# AT_Link_V1_4.net
KiCad netlist of a schematic drawn in Altium Designer
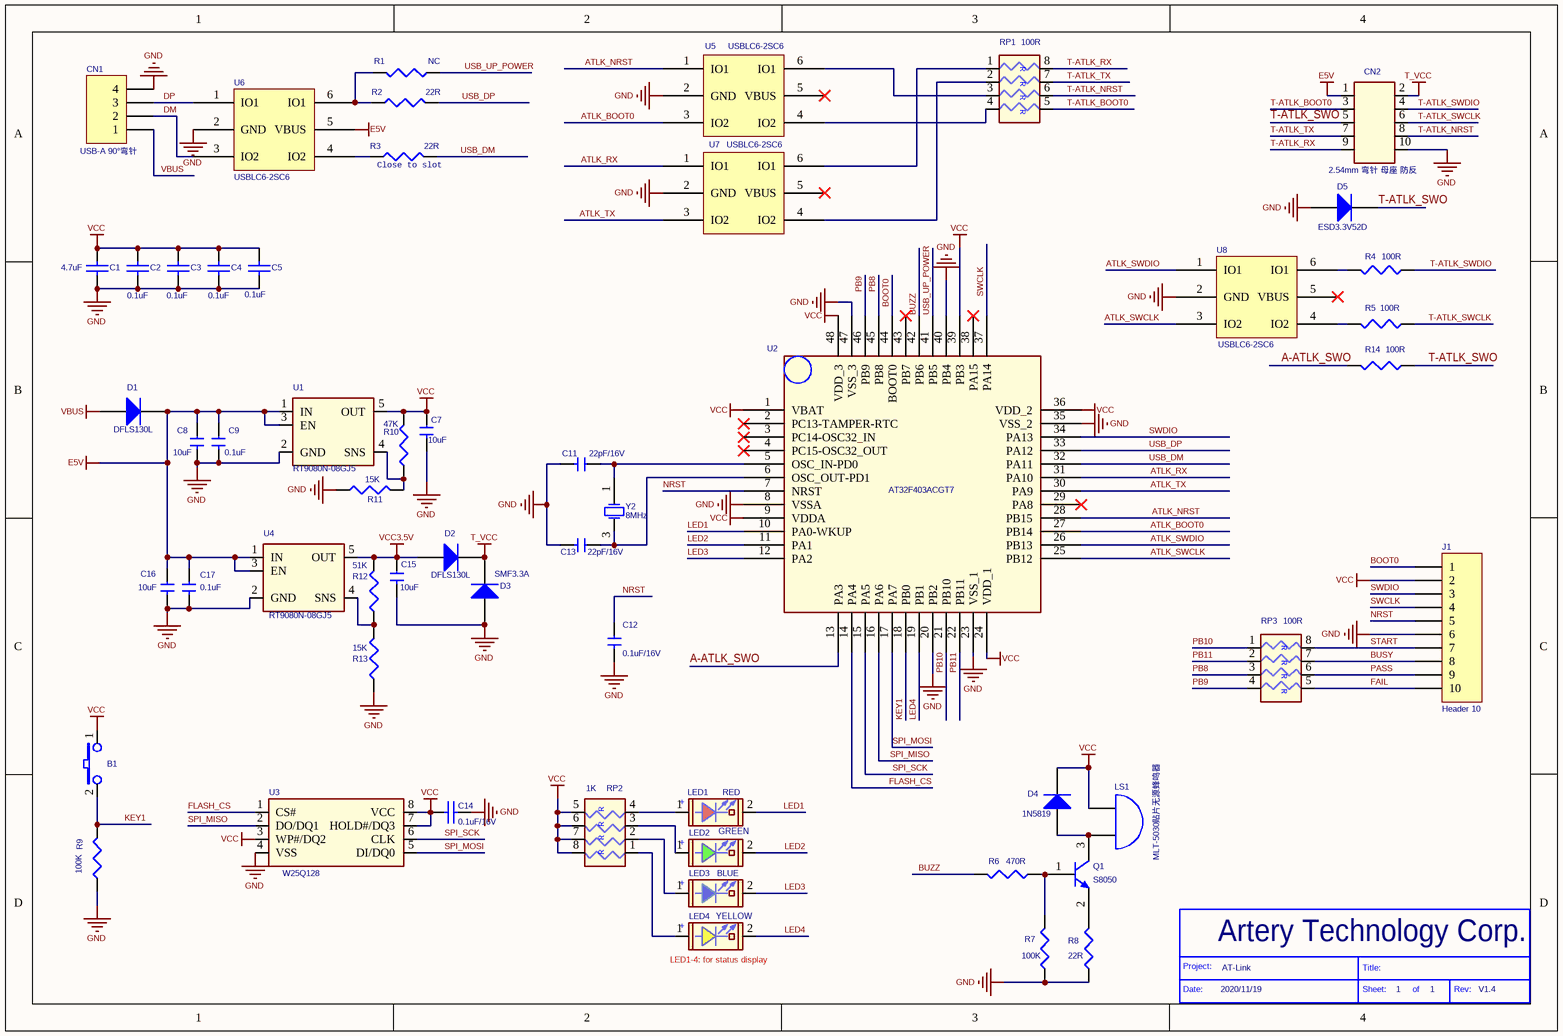
[diagram p0: AT_Link_V1.4.SchDoc]

(export (version "E")
  (design (tool "Eeschema 10.0.6"))
  (components
    (comp (ref "B1")
      (value "PB,Blue,SMD_2P")
      (description "3*6*5")
      (libsource (lib "*") (part "Push_Bottom,Blue,SMD_2P"))
    )
    (comp (ref "C1")
      (value "4.7uF")
      (footprint "C0603")
      (description "Capacitor (Semiconductor SIM Model)")
      (fields (field (name "PUBLISHER") "Altium Limited"))
      (libsource (lib "PcbLib") (part "Cap Semi"))
    )
    (comp (ref "C2")
      (value "0.1uF")
      (footprint "C0603")
      (description "Capacitor (Semiconductor SIM Model)")
      (fields (field (name "PUBLISHER") "Altium Limited"))
      (libsource (lib "PcbLib") (part "Cap Semi"))
    )
    (comp (ref "C3")
      (value "0.1uF")
      (footprint "C0603")
      (description "Capacitor (Semiconductor SIM Model)")
      (fields (field (name "PUBLISHER") "Altium Limited"))
      (libsource (lib "PcbLib") (part "Cap Semi"))
    )
    (comp (ref "C4")
      (value "0.1uF")
      (footprint "C0603")
      (description "Capacitor (Semiconductor SIM Model)")
      (fields (field (name "PUBLISHER") "Altium Limited"))
      (libsource (lib "PcbLib") (part "Cap Semi"))
    )
    (comp (ref "C5")
      (value "0.1uF")
      (footprint "C0603")
      (description "Capacitor (Semiconductor SIM Model)")
      (fields (field (name "PUBLISHER") "Altium Limited"))
      (libsource (lib "PcbLib") (part "Cap Semi"))
    )
    (comp (ref "C7") (value "10uF") (libsource (lib "*") (part "0.1uF,50V,20%,SMD0603")))
    (comp (ref "C8") (value "10uF") (libsource (lib "*") (part "0.1uF,50V,20%,SMD0603")))
    (comp (ref "C9") (value "0.1uF") (libsource (lib "*") (part "0.1uF,50V,20%,SMD0603")))
    (comp (ref "C11") (value "22pF/16V") (libsource (lib "*") (part "10pF,50V,5%,SMD0603")))
    (comp (ref "C12") (value "0.1uF/16V") (libsource (lib "*") (part "0.1uF,50V,20%,SMD0603")))
    (comp (ref "C13") (value "22pF/16V") (libsource (lib "*") (part "10pF,50V,5%,SMD0603")))
    (comp (ref "C14")
      (value "0.1uF/16V")
      (footprint "C0603")
      (description "Capacitor (Semiconductor SIM Model)")
      (fields (field (name "PUBLISHER") "Altium Limited"))
      (libsource (lib "PcbLib") (part "Cap Semi"))
    )
    (comp (ref "C15") (value "10uF") (libsource (lib "*") (part "0.1uF,50V,20%,SMD0603")))
    (comp (ref "C16") (value "10uF") (libsource (lib "*") (part "0.1uF,50V,20%,SMD0603")))
    (comp (ref "C17") (value "0.1uF") (libsource (lib "*") (part "0.1uF,50V,20%,SMD0603")))
    (comp (ref "CN1")
      (value "USB-A 90°弯针")
      (footprint "USB_A - Dip")
      (description "Header, 4-Pin")
      (fields (field (name "PUBLISHER") "Altium Limited"))
      (libsource (lib "Miscellaneous Connectors") (part "Header 4"))
    )
    (comp (ref "CN2") (value "CON1") (footprint "SWD_2*5P_SMT") (libsource (lib "*") (part "CON10A_0")))
    (comp (ref "D1")
      (value "DFLS130L")
      (footprint "SOD-123")
      (description "Default Diode")
      (fields (field (name "PUBLISHER") "Altium Limited"))
      (libsource (lib "Miscellaneous Devices") (part "Diode"))
    )
    (comp (ref "D2")
      (value "DFLS130L")
      (footprint "SOD-123")
      (description "Default Diode")
      (fields (field (name "PUBLISHER") "Altium Limited"))
      (libsource (lib "Miscellaneous Devices") (part "Diode"))
    )
    (comp (ref "D3")
      (value "SMF3.3A")
      (footprint "SOD-123")
      (description "Default Diode")
      (fields (field (name "PUBLISHER") "Altium Limited"))
      (libsource (lib "Miscellaneous Devices") (part "Diode"))
    )
    (comp (ref "D4")
      (value "1N5819")
      (footprint "LED0603")
      (description "Default Diode")
      (fields (field (name "PUBLISHER") "Altium Limited"))
      (libsource (lib "Miscellaneous Devices") (part "Diode"))
    )
    (comp (ref "D5")
      (value "ESD3.3V52D")
      (footprint "SOD523")
      (description "Default Diode")
      (fields (field (name "PUBLISHER") "Altium Limited"))
      (libsource (lib "Miscellaneous Devices") (part "Diode"))
    )
    (comp (ref "J1")
      (value "Header 10")
      (footprint "HDR1X10")
      (description "Header, 10-Pin")
      (fields (field (name "PUBLISHER") "Altium Limited"))
      (libsource (lib "Miscellaneous Connectors") (part "Header 10"))
    )
    (comp (ref "LED1")
      (value "RED")
      (footprint "LED0603")
      (libsource (lib "AT32F403_TINY_LQFP144_Library") (part "RED,SMD0603"))
    )
    (comp (ref "LED2")
      (value "GREEN")
      (footprint "LED0603")
      (libsource (lib "AT32F403_TINY_LQFP144_Library") (part "GREEN,SMD0603"))
    )
    (comp (ref "LED3")
      (value "BLUE")
      (footprint "LED0603")
      (description "贴片LED 蓝色 0603")
      (libsource (lib "AT_START_F415") (part "BLUE,SMD0603"))
    )
    (comp (ref "LED4")
      (value "YELLOW")
      (footprint "LED0603")
      (libsource (lib "Schlib1") (part "YELLOW,SMD0603"))
    )
    (comp (ref "LS1")
      (value "MLT-5030贴片无源蜂鸣器")
      (footprint "BUZZER - 5030")
      (description "Electrical Bell")
      (fields (field (name "PUBLISHER") "Altium Limited"))
      (libsource (lib "Miscellaneous Devices") (part "Bell"))
    )
    (comp (ref "Q1") (value "S8050") (footprint "SOT-23") (libsource (lib "Schlib") (part "NPN")))
    (comp (ref "R1") (value "NC") (libsource (lib "*") (part "10K,1/10W,1%,SMD0603_Dup1")))
    (comp (ref "R2") (value "22R") (libsource (lib "*") (part "22,1/10W,1%,SMD0603")))
    (comp (ref "R3") (value "22R") (libsource (lib "*") (part "22,1/10W,1%,SMD0603")))
    (comp (ref "R4") (value "100R") (libsource (lib "*") (part "22,1/10W,1%,SMD0603")))
    (comp (ref "R5") (value "100R") (libsource (lib "*") (part "22,1/10W,1%,SMD0603")))
    (comp (ref "R6") (value "470R") (libsource (lib "*") (part "470,1/10W,1%,SMD0603")))
    (comp (ref "R7") (value "100K") (libsource (lib "*") (part "470,1/10W,1%,SMD0603")))
    (comp (ref "R8") (value "22R") (libsource (lib "*") (part "470,1/10W,1%,SMD0603")))
    (comp (ref "R9") (value "100K") (libsource (lib "*") (part "10K,1/10W,1%,SMD0603")))
    (comp (ref "R10") (value "47K") (libsource (lib "*") (part "470,1/10W,1%,SMD0603")))
    (comp (ref "R11") (value "15K") (libsource (lib "*") (part "470,1/10W,1%,SMD0603")))
    (comp (ref "R12") (value "51K") (libsource (lib "*") (part "470,1/10W,1%,SMD0603")))
    (comp (ref "R13") (value "15K") (libsource (lib "*") (part "470,1/10W,1%,SMD0603")))
    (comp (ref "R14") (value "100R") (libsource (lib "*") (part "22,1/10W,1%,SMD0603")))
    (comp (ref "RP1") (value "100R") (libsource (lib "") (part "22,1/16W,5%,8P4R_1")))
    (comp (ref "RP2") (value "1K") (libsource (lib "*") (part "22,1/16W,5%,8P4R")))
    (comp (ref "RP3") (value "100R") (libsource (lib "") (part "22,1/16W,5%,8P4R_1")))
    (comp (ref "U1") (value "RT9080N-08GJ5") (libsource (lib "SCM_START_402F") (part "RT9080N")))
    (comp (ref "U2")
      (value "AT32F403ACGT7")
      (footprint "AT403-ALL-PcbLib:LQFP48 - 2")
      (libsource (lib "AT403-ALL-Package") (part "LQFP48&QFN48"))
    )
    (comp (ref "U3")
      (value "W25Q128")
      (footprint "SOIC8_208")
      (libsource (lib "AT32F403_TINY_LQFP144_Library") (part "W25Q128FVSIQ,SOIC8_1"))
    )
    (comp (ref "U4") (value "RT9080N-08GJ5") (libsource (lib "SCM_START_402F") (part "RT9080N")))
    (comp (ref "U5")
      (value "USBLC6-2SC6")
      (footprint "SOT23_6P - L")
      (libsource (lib "Schlib1") (part "USBLC6-2SC6"))
    )
    (comp (ref "U6")
      (value "USBLC6-2SC6")
      (footprint "SOT23_6P - L")
      (libsource (lib "Schlib1") (part "USBLC6-2SC6"))
    )
    (comp (ref "U7")
      (value "USBLC6-2SC6")
      (footprint "SOT23_6P - L")
      (libsource (lib "Schlib1") (part "USBLC6-2SC6"))
    )
    (comp (ref "U8")
      (value "USBLC6-2SC6")
      (footprint "SOT23_6P - L")
      (libsource (lib "Schlib1") (part "USBLC6-2SC6"))
    )
    (comp (ref "Y2")
      (value "8MHz")
      (footprint "XTAL_5032")
      (description "贴片晶振")
      (libsource (lib "Artery_Wanbing") (part "SMD-5032_4P  8MHZ 20PF 10PPM"))
    )
  )
  (nets
    (net (code "1") (name "/A-ATLK_SWO") (class "Default")
      (node (ref "R14") (pin "2") (pinfunction "2_2") (pintype "passive"))
      (node (ref "U2") (pin "13") (pinfunction "PA3_13") (pintype "passive"))
    )
    (net (code "2") (name "/ATLK_BOOT0") (class "Default")
      (node (ref "U2") (pin "27") (pinfunction "PB14_27") (pintype "passive"))
      (node (ref "U5") (pin "3") (pinfunction "IO2_3") (pintype "passive"))
    )
    (net (code "3") (name "/ATLK_NRST") (class "Default")
      (node (ref "U2") (pin "28") (pinfunction "PB15_28") (pintype "passive"))
      (node (ref "U5") (pin "1") (pinfunction "IO1_1") (pintype "passive"))
    )
    (net (code "4") (name "/ATLK_RX") (class "Default")
      (node (ref "U2") (pin "31") (pinfunction "PA10_31") (pintype "passive"))
      (node (ref "U7") (pin "1") (pinfunction "IO1_1") (pintype "passive"))
    )
    (net (code "5") (name "/ATLK_SWCLK") (class "Default")
      (node (ref "U2") (pin "25") (pinfunction "PB12_25") (pintype "passive"))
      (node (ref "U8") (pin "3") (pinfunction "IO2_3") (pintype "passive"))
    )
    (net (code "6") (name "/ATLK_SWDIO") (class "Default")
      (node (ref "U2") (pin "26") (pinfunction "PB13_26") (pintype "passive"))
      (node (ref "U8") (pin "1") (pinfunction "IO1_1") (pintype "passive"))
    )
    (net (code "7") (name "/ATLK_TX") (class "Default")
      (node (ref "U2") (pin "30") (pinfunction "PA9_30") (pintype "passive"))
      (node (ref "U7") (pin "3") (pinfunction "IO2_3") (pintype "passive"))
    )
    (net (code "8") (name "/BOOT0") (class "Default")
      (node (ref "J1") (pin "1") (pinfunction "1_1") (pintype "passive"))
      (node (ref "U2") (pin "44") (pinfunction "BOOT0_44") (pintype "passive"))
    )
    (net (code "9") (name "/BUSY") (class "Default")
      (node (ref "J1") (pin "8") (pinfunction "8_8") (pintype "passive"))
      (node (ref "RP3") (pin "7") (pinfunction "7_7") (pintype "passive"))
    )
    (net (code "10") (name "/BUZZ") (class "Default")
      (node (ref "R6") (pin "2") (pinfunction "2_2") (pintype "passive"))
      (node (ref "U2") (pin "42") (pinfunction "PB6_42") (pintype "passive"))
    )
    (net (code "11") (name "/DM") (class "Default")
      (node (ref "CN1") (pin "2") (pinfunction "2_2") (pintype "passive"))
      (node (ref "U6") (pin "3") (pinfunction "IO2_3") (pintype "passive"))
    )
    (net (code "12") (name "/DP") (class "Default")
      (node (ref "CN1") (pin "3") (pinfunction "3_3") (pintype "passive"))
      (node (ref "U6") (pin "1") (pinfunction "IO1_1") (pintype "passive"))
    )
    (net (code "13") (name "/FAIL") (class "Default")
      (node (ref "J1") (pin "10") (pinfunction "10_10") (pintype "passive"))
      (node (ref "RP3") (pin "5") (pinfunction "5_5") (pintype "passive"))
    )
    (net (code "14") (name "/FLASH_CS") (class "Default")
      (node (ref "U2") (pin "14") (pinfunction "PA4_14") (pintype "passive"))
      (node (ref "U3") (pin "1") (pinfunction "CS#_1") (pintype "passive"))
    )
    (net (code "15") (name "/KEY1") (class "Default")
      (node (ref "B1") (pin "2") (pinfunction "2_2") (pintype "passive"))
      (node (ref "R9") (pin "2") (pinfunction "2_2") (pintype "passive"))
      (node (ref "U2") (pin "18") (pinfunction "PB0_18") (pintype "passive"))
    )
    (net (code "16") (name "/LED1") (class "Default")
      (node (ref "LED1") (pin "2") (pinfunction "CATHODE_2") (pintype "passive"))
      (node (ref "U2") (pin "10") (pinfunction "PA0-WKUP_10") (pintype "passive"))
    )
    (net (code "17") (name "/LED2") (class "Default")
      (node (ref "LED2") (pin "2") (pinfunction "CATHODE_2") (pintype "passive"))
      (node (ref "U2") (pin "11") (pinfunction "PA1_11") (pintype "passive"))
    )
    (net (code "18") (name "/LED3") (class "Default")
      (node (ref "LED3") (pin "2") (pinfunction "CATHODE_2") (pintype "passive"))
      (node (ref "U2") (pin "12") (pinfunction "PA2_12") (pintype "passive"))
    )
    (net (code "19") (name "/LED4") (class "Default")
      (node (ref "LED4") (pin "2") (pinfunction "CATHODE_2") (pintype "passive"))
      (node (ref "U2") (pin "19") (pinfunction "PB1_19") (pintype "passive"))
    )
    (net (code "20") (name "/NRST") (class "Default")
      (node (ref "C12") (pin "1") (pinfunction "1_1") (pintype "passive"))
      (node (ref "J1") (pin "5") (pinfunction "5_5") (pintype "passive"))
      (node (ref "U2") (pin "7") (pinfunction "NRST_7") (pintype "passive"))
    )
    (net (code "21") (name "/PASS") (class "Default")
      (node (ref "J1") (pin "9") (pinfunction "9_9") (pintype "passive"))
      (node (ref "RP3") (pin "6") (pinfunction "6_6") (pintype "passive"))
    )
    (net (code "22") (name "/PB8") (class "Default")
      (node (ref "RP3") (pin "3") (pinfunction "3_3") (pintype "passive"))
      (node (ref "U2") (pin "45") (pinfunction "PB8_45") (pintype "passive"))
    )
    (net (code "23") (name "/PB9") (class "Default")
      (node (ref "RP3") (pin "4") (pinfunction "4_4") (pintype "passive"))
      (node (ref "U2") (pin "46") (pinfunction "PB9_46") (pintype "passive"))
    )
    (net (code "24") (name "/PB10") (class "Default")
      (node (ref "RP3") (pin "1") (pinfunction "1_1") (pintype "passive"))
      (node (ref "U2") (pin "21") (pinfunction "PB10_21") (pintype "passive"))
    )
    (net (code "25") (name "/PB11") (class "Default")
      (node (ref "RP3") (pin "2") (pinfunction "2_2") (pintype "passive"))
      (node (ref "U2") (pin "22") (pinfunction "PB11_22") (pintype "passive"))
    )
    (net (code "26") (name "/SPI_MISO") (class "Default")
      (node (ref "U2") (pin "16") (pinfunction "PA6_16") (pintype "passive"))
      (node (ref "U3") (pin "2") (pinfunction "DO/DQ1_2") (pintype "passive"))
    )
    (net (code "27") (name "/SPI_MOSI") (class "Default")
      (node (ref "U2") (pin "17") (pinfunction "PA7_17") (pintype "passive"))
      (node (ref "U3") (pin "5") (pinfunction "DI/DQ0_5") (pintype "passive"))
    )
    (net (code "28") (name "/SPI_SCK") (class "Default")
      (node (ref "U2") (pin "15") (pinfunction "PA5_15") (pintype "passive"))
      (node (ref "U3") (pin "6") (pinfunction "CLK_6") (pintype "passive"))
    )
    (net (code "29") (name "/START") (class "Default")
      (node (ref "J1") (pin "7") (pinfunction "7_7") (pintype "passive"))
      (node (ref "RP3") (pin "8") (pinfunction "8_8") (pintype "passive"))
    )
    (net (code "30") (name "/SWCLK") (class "Default")
      (node (ref "J1") (pin "4") (pinfunction "4_4") (pintype "passive"))
      (node (ref "U2") (pin "37") (pinfunction "PA14_37") (pintype "passive"))
    )
    (net (code "31") (name "/SWDIO") (class "Default")
      (node (ref "J1") (pin "3") (pinfunction "3_3") (pintype "passive"))
      (node (ref "U2") (pin "34") (pinfunction "PA13_34") (pintype "passive"))
    )
    (net (code "32") (name "/T-ATLK_BOOT0") (class "Default")
      (node (ref "CN2") (pin "3") (pinfunction "3_3") (pintype "passive"))
      (node (ref "RP1") (pin "5") (pinfunction "5_5") (pintype "passive"))
    )
    (net (code "33") (name "/T-ATLK_NRST") (class "Default")
      (node (ref "CN2") (pin "8") (pinfunction "8_8") (pintype "passive"))
      (node (ref "RP1") (pin "6") (pinfunction "6_6") (pintype "passive"))
    )
    (net (code "34") (name "/T-ATLK_RX") (class "Default")
      (node (ref "CN2") (pin "9") (pinfunction "9_9") (pintype "passive"))
      (node (ref "RP1") (pin "8") (pinfunction "8_8") (pintype "passive"))
    )
    (net (code "35") (name "/T-ATLK_SWCLK") (class "Default")
      (node (ref "CN2") (pin "6") (pinfunction "6_6") (pintype "passive"))
      (node (ref "R5") (pin "1") (pinfunction "1_1") (pintype "passive"))
    )
    (net (code "36") (name "/T-ATLK_SWDIO") (class "Default")
      (node (ref "CN2") (pin "4") (pinfunction "4_4") (pintype "passive"))
      (node (ref "R4") (pin "1") (pinfunction "1_1") (pintype "passive"))
    )
    (net (code "37") (name "/T-ATLK_SWO") (class "Default")
      (node (ref "CN2") (pin "5") (pinfunction "5_5") (pintype "passive"))
      (node (ref "D5") (pin "2") (pinfunction "K_2") (pintype "passive"))
      (node (ref "R14") (pin "1") (pinfunction "1_1") (pintype "passive"))
    )
    (net (code "38") (name "/T-ATLK_TX") (class "Default")
      (node (ref "CN2") (pin "7") (pinfunction "7_7") (pintype "passive"))
      (node (ref "RP1") (pin "7") (pinfunction "7_7") (pintype "passive"))
    )
    (net (code "39") (name "/USB_DM") (class "Default")
      (node (ref "R3") (pin "2") (pinfunction "2_2") (pintype "passive"))
      (node (ref "U2") (pin "32") (pinfunction "PA11_32") (pintype "passive"))
    )
    (net (code "40") (name "/USB_DP") (class "Default")
      (node (ref "R2") (pin "2") (pinfunction "2_2") (pintype "passive"))
      (node (ref "U2") (pin "33") (pinfunction "PA12_33") (pintype "passive"))
    )
    (net (code "41") (name "/USB_UP_POWER") (class "Default")
      (node (ref "R1") (pin "1") (pinfunction "1_1") (pintype "passive"))
      (node (ref "U2") (pin "41") (pinfunction "PB5_41") (pintype "passive"))
    )
    (net (code "42") (name "E5V") (class "Default")
      (node (ref "C16") (pin "1") (pinfunction "1_1") (pintype "passive"))
      (node (ref "C17") (pin "1") (pinfunction "1_1") (pintype "passive"))
      (node (ref "C8") (pin "1") (pinfunction "1_1") (pintype "passive"))
      (node (ref "C9") (pin "1") (pinfunction "1_1") (pintype "passive"))
      (node (ref "CN2") (pin "1") (pinfunction "1_1") (pintype "passive"))
      (node (ref "D1") (pin "2") (pinfunction "K_2") (pintype "passive"))
      (node (ref "U1") (pin "1") (pinfunction "IN_1") (pintype "power_in"))
      (node (ref "U1") (pin "3") (pinfunction "EN_3") (pintype "passive"))
      (node (ref "U4") (pin "1") (pinfunction "IN_1") (pintype "power_in"))
      (node (ref "U4") (pin "3") (pinfunction "EN_3") (pintype "passive"))
      (node (ref "U6") (pin "5") (pinfunction "VBUS_5") (pintype "passive"))
    )
    (net (code "43") (name "GND") (class "Default")
      (node (ref "C1") (pin "1") (pinfunction "1_1") (pintype "passive"))
      (node (ref "C11") (pin "2") (pinfunction "2_2") (pintype "passive"))
      (node (ref "C12") (pin "2") (pinfunction "2_2") (pintype "passive"))
      (node (ref "C13") (pin "2") (pinfunction "2_2") (pintype "passive"))
      (node (ref "C14") (pin "1") (pinfunction "1_1") (pintype "passive"))
      (node (ref "C15") (pin "2") (pinfunction "2_2") (pintype "passive"))
      (node (ref "C16") (pin "2") (pinfunction "2_2") (pintype "passive"))
      (node (ref "C17") (pin "2") (pinfunction "2_2") (pintype "passive"))
      (node (ref "C2") (pin "1") (pinfunction "1_1") (pintype "passive"))
      (node (ref "C3") (pin "1") (pinfunction "1_1") (pintype "passive"))
      (node (ref "C4") (pin "1") (pinfunction "1_1") (pintype "passive"))
      (node (ref "C5") (pin "1") (pinfunction "1_1") (pintype "passive"))
      (node (ref "C7") (pin "2") (pinfunction "2_2") (pintype "passive"))
      (node (ref "C8") (pin "2") (pinfunction "2_2") (pintype "passive"))
      (node (ref "C9") (pin "2") (pinfunction "2_2") (pintype "passive"))
      (node (ref "CN1") (pin "4") (pinfunction "4_4") (pintype "passive"))
      (node (ref "CN2") (pin "10") (pinfunction "10_10") (pintype "passive"))
      (node (ref "D3") (pin "1") (pinfunction "A_1") (pintype "passive"))
      (node (ref "D5") (pin "1") (pinfunction "A_1") (pintype "passive"))
      (node (ref "J1") (pin "6") (pinfunction "6_6") (pintype "passive"))
      (node (ref "R11") (pin "1") (pinfunction "1_1") (pintype "passive"))
      (node (ref "R13") (pin "1") (pinfunction "1_1") (pintype "passive"))
      (node (ref "R7") (pin "1") (pinfunction "1_1") (pintype "passive"))
      (node (ref "R8") (pin "1") (pinfunction "1_1") (pintype "passive"))
      (node (ref "R9") (pin "1") (pinfunction "1_1") (pintype "passive"))
      (node (ref "U1") (pin "2") (pinfunction "GND_2") (pintype "power_in"))
      (node (ref "U2") (pin "20") (pinfunction "PB2_20") (pintype "passive"))
      (node (ref "U2") (pin "23") (pinfunction "VSS_1_23") (pintype "passive"))
      (node (ref "U2") (pin "35") (pinfunction "VSS_2_35") (pintype "passive"))
      (node (ref "U2") (pin "40") (pinfunction "PB4_40") (pintype "passive"))
      (node (ref "U2") (pin "47") (pinfunction "VSS_3_47") (pintype "passive"))
      (node (ref "U2") (pin "8") (pinfunction "VSSA_8") (pintype "passive"))
      (node (ref "U3") (pin "4") (pinfunction "VSS_4") (pintype "power_in"))
      (node (ref "U4") (pin "2") (pinfunction "GND_2") (pintype "power_in"))
      (node (ref "U5") (pin "2") (pinfunction "GND_2") (pintype "passive"))
      (node (ref "U6") (pin "2") (pinfunction "GND_2") (pintype "passive"))
      (node (ref "U7") (pin "2") (pinfunction "GND_2") (pintype "passive"))
      (node (ref "U8") (pin "2") (pinfunction "GND_2") (pintype "passive"))
    )
    (net (code "44") (name "Net-(D4-A)") (class "Default")
      (node (ref "D4") (pin "1") (pinfunction "A_1") (pintype "passive"))
      (node (ref "LS1") (pin "2") (pinfunction "B_2") (pintype "passive"))
      (node (ref "Q1") (pin "3") (pinfunction "C_3") (pintype "passive"))
    )
    (net (code "45") (name "Net-(LED1-ANODE)") (class "Default")
      (node (ref "LED1") (pin "1") (pinfunction "ANODE_1") (pintype "passive"))
      (node (ref "RP2") (pin "4") (pinfunction "4_4") (pintype "passive"))
    )
    (net (code "46") (name "Net-(LED2-ANODE)") (class "Default")
      (node (ref "LED2") (pin "1") (pinfunction "ANODE_1") (pintype "passive"))
      (node (ref "RP2") (pin "3") (pinfunction "3_3") (pintype "passive"))
    )
    (net (code "47") (name "Net-(LED3-ANODE)") (class "Default")
      (node (ref "LED3") (pin "1") (pinfunction "ANODE_1") (pintype "passive"))
      (node (ref "RP2") (pin "2") (pinfunction "2_2") (pintype "passive"))
    )
    (net (code "48") (name "Net-(LED4-ANODE)") (class "Default")
      (node (ref "LED4") (pin "1") (pinfunction "ANODE_1") (pintype "passive"))
      (node (ref "RP2") (pin "1") (pinfunction "1_1") (pintype "passive"))
    )
    (net (code "49") (name "Net-(Q1-B)") (class "Default")
      (node (ref "Q1") (pin "1") (pinfunction "B_1") (pintype "passive"))
      (node (ref "R6") (pin "1") (pinfunction "1_1") (pintype "passive"))
      (node (ref "R7") (pin "2") (pinfunction "2_2") (pintype "passive"))
    )
    (net (code "50") (name "Net-(Q1-E)") (class "Default")
      (node (ref "Q1") (pin "2") (pinfunction "E_2") (pintype "passive"))
      (node (ref "R8") (pin "2") (pinfunction "2_2") (pintype "passive"))
    )
    (net (code "51") (name "Net-(R1-Pad2)") (class "Default")
      (node (ref "R1") (pin "2") (pinfunction "2_2") (pintype "passive"))
      (node (ref "R2") (pin "1") (pinfunction "1_1") (pintype "passive"))
      (node (ref "U6") (pin "6") (pinfunction "IO1_6") (pintype "passive"))
    )
    (net (code "52") (name "Net-(R3-Pad1)") (class "Default")
      (node (ref "R3") (pin "1") (pinfunction "1_1") (pintype "passive"))
      (node (ref "U6") (pin "4") (pinfunction "IO2_4") (pintype "passive"))
    )
    (net (code "53") (name "Net-(R4-Pad2)") (class "Default")
      (node (ref "R4") (pin "2") (pinfunction "2_2") (pintype "passive"))
      (node (ref "U8") (pin "6") (pinfunction "IO1_6") (pintype "passive"))
    )
    (net (code "54") (name "Net-(R5-Pad2)") (class "Default")
      (node (ref "R5") (pin "2") (pinfunction "2_2") (pintype "passive"))
      (node (ref "U8") (pin "4") (pinfunction "IO2_4") (pintype "passive"))
    )
    (net (code "55") (name "Net-(RP1-Pad1)") (class "Default")
      (node (ref "RP1") (pin "1") (pinfunction "1_1") (pintype "passive"))
      (node (ref "U7") (pin "6") (pinfunction "IO1_6") (pintype "passive"))
    )
    (net (code "56") (name "Net-(RP1-Pad2)") (class "Default")
      (node (ref "RP1") (pin "2") (pinfunction "2_2") (pintype "passive"))
      (node (ref "U7") (pin "4") (pinfunction "IO2_4") (pintype "passive"))
    )
    (net (code "57") (name "Net-(RP1-Pad3)") (class "Default")
      (node (ref "RP1") (pin "3") (pinfunction "3_3") (pintype "passive"))
      (node (ref "U5") (pin "6") (pinfunction "IO1_6") (pintype "passive"))
    )
    (net (code "58") (name "Net-(RP1-Pad4)") (class "Default")
      (node (ref "RP1") (pin "4") (pinfunction "4_4") (pintype "passive"))
      (node (ref "U5") (pin "4") (pinfunction "IO2_4") (pintype "passive"))
    )
    (net (code "59") (name "Net-(U1-SNS)") (class "Default")
      (node (ref "R10") (pin "1") (pinfunction "1_1") (pintype "passive"))
      (node (ref "R11") (pin "2") (pinfunction "2_2") (pintype "passive"))
      (node (ref "U1") (pin "4") (pinfunction "SNS_4") (pintype "passive"))
    )
    (net (code "60") (name "Net-(U2-OSC_IN-PD0)") (class "Default")
      (node (ref "C11") (pin "1") (pinfunction "1_1") (pintype "passive"))
      (node (ref "U2") (pin "5") (pinfunction "OSC_IN-PD0_5") (pintype "passive"))
      (node (ref "Y2") (pin "1") (pinfunction "OSC1_1") (pintype "passive"))
    )
    (net (code "61") (name "Net-(U2-OSC_OUT-PD1)") (class "Default")
      (node (ref "C13") (pin "1") (pinfunction "1_1") (pintype "passive"))
      (node (ref "U2") (pin "6") (pinfunction "OSC_OUT-PD1_6") (pintype "passive"))
      (node (ref "Y2") (pin "3") (pinfunction "OSC2_3") (pintype "passive"))
    )
    (net (code "62") (name "Net-(U4-SNS)") (class "Default")
      (node (ref "R12") (pin "1") (pinfunction "1_1") (pintype "passive"))
      (node (ref "R13") (pin "2") (pinfunction "2_2") (pintype "passive"))
      (node (ref "U4") (pin "4") (pinfunction "SNS_4") (pintype "passive"))
    )
    (net (code "63") (name "T_VCC") (class "Default")
      (node (ref "CN2") (pin "2") (pinfunction "2_2") (pintype "passive"))
      (node (ref "D2") (pin "2") (pinfunction "K_2") (pintype "passive"))
      (node (ref "D3") (pin "2") (pinfunction "K_2") (pintype "passive"))
    )
    (net (code "64") (name "VBUS") (class "Default")
      (node (ref "CN1") (pin "1") (pinfunction "1_1") (pintype "passive"))
      (node (ref "D1") (pin "1") (pinfunction "A_1") (pintype "passive"))
    )
    (net (code "65") (name "VCC") (class "Default")
      (node (ref "B1") (pin "1") (pinfunction "1_1") (pintype "passive"))
      (node (ref "C1") (pin "2") (pinfunction "2_2") (pintype "passive"))
      (node (ref "C14") (pin "2") (pinfunction "2_2") (pintype "passive"))
      (node (ref "C2") (pin "2") (pinfunction "2_2") (pintype "passive"))
      (node (ref "C3") (pin "2") (pinfunction "2_2") (pintype "passive"))
      (node (ref "C4") (pin "2") (pinfunction "2_2") (pintype "passive"))
      (node (ref "C5") (pin "2") (pinfunction "2_2") (pintype "passive"))
      (node (ref "C7") (pin "1") (pinfunction "1_1") (pintype "passive"))
      (node (ref "D4") (pin "2") (pinfunction "K_2") (pintype "passive"))
      (node (ref "J1") (pin "2") (pinfunction "2_2") (pintype "passive"))
      (node (ref "LS1") (pin "1") (pinfunction "A_1") (pintype "passive"))
      (node (ref "R10") (pin "2") (pinfunction "2_2") (pintype "passive"))
      (node (ref "RP2") (pin "5") (pinfunction "5_5") (pintype "passive"))
      (node (ref "RP2") (pin "6") (pinfunction "6_6") (pintype "passive"))
      (node (ref "RP2") (pin "7") (pinfunction "7_7") (pintype "passive"))
      (node (ref "RP2") (pin "8") (pinfunction "8_8") (pintype "passive"))
      (node (ref "U1") (pin "5") (pinfunction "OUT_5") (pintype "power_in"))
      (node (ref "U2") (pin "1") (pinfunction "VBAT_1") (pintype "passive"))
      (node (ref "U2") (pin "24") (pinfunction "VDD_1_24") (pintype "passive"))
      (node (ref "U2") (pin "36") (pinfunction "VDD_2_36") (pintype "passive"))
      (node (ref "U2") (pin "39") (pinfunction "PB3_39") (pintype "passive"))
      (node (ref "U2") (pin "48") (pinfunction "VDD_3_48") (pintype "passive"))
      (node (ref "U2") (pin "9") (pinfunction "VDDA_9") (pintype "passive"))
      (node (ref "U3") (pin "3") (pinfunction "WP#/DQ2_3") (pintype "passive"))
      (node (ref "U3") (pin "7") (pinfunction "HOLD#/DQ3_7") (pintype "passive"))
      (node (ref "U3") (pin "8") (pinfunction "VCC_8") (pintype "power_in"))
    )
    (net (code "66") (name "VCC3.5V") (class "Default")
      (node (ref "C15") (pin "1") (pinfunction "1_1") (pintype "passive"))
      (node (ref "D2") (pin "1") (pinfunction "A_1") (pintype "passive"))
      (node (ref "R12") (pin "2") (pinfunction "2_2") (pintype "passive"))
      (node (ref "U4") (pin "5") (pinfunction "OUT_5") (pintype "power_in"))
    )
    (net (code "67") (name "unconnected-(U2-PA8-Pad29)") (class "Default")
      (node (ref "U2") (pin "29") (pinfunction "PA8_29") (pintype "passive+no_connect"))
    )
    (net (code "68") (name "unconnected-(U2-PA15-Pad38)") (class "Default")
      (node (ref "U2") (pin "38") (pinfunction "PA15_38") (pintype "passive+no_connect"))
    )
    (net (code "69") (name "unconnected-(U2-PB7-Pad43)") (class "Default")
      (node (ref "U2") (pin "43") (pinfunction "PB7_43") (pintype "passive+no_connect"))
    )
    (net (code "70") (name "unconnected-(U2-PC13-TAMPER-RTC-Pad2)") (class "Default")
      (node (ref "U2") (pin "2") (pinfunction "PC13-TAMPER-RTC_2") (pintype "passive+no_connect"))
    )
    (net (code "71") (name "unconnected-(U2-PC14-OSC32_IN-Pad3)") (class "Default")
      (node (ref "U2") (pin "3") (pinfunction "PC14-OSC32_IN_3") (pintype "passive+no_connect"))
    )
    (net (code "72") (name "unconnected-(U2-PC15-OSC32_OUT-Pad4)") (class "Default")
      (node (ref "U2") (pin "4") (pinfunction "PC15-OSC32_OUT_4") (pintype "passive+no_connect"))
    )
    (net (code "73") (name "unconnected-(U5-VBUS-Pad5)") (class "Default")
      (node (ref "U5") (pin "5") (pinfunction "VBUS_5") (pintype "passive+no_connect"))
    )
    (net (code "74") (name "unconnected-(U7-VBUS-Pad5)") (class "Default")
      (node (ref "U7") (pin "5") (pinfunction "VBUS_5") (pintype "passive+no_connect"))
    )
    (net (code "75") (name "unconnected-(U8-VBUS-Pad5)") (class "Default")
      (node (ref "U8") (pin "5") (pinfunction "VBUS_5") (pintype "passive+no_connect"))
    )
  )
)
